# circuito_v4.net
KiCad netlist of a schematic drawn in EAGLE
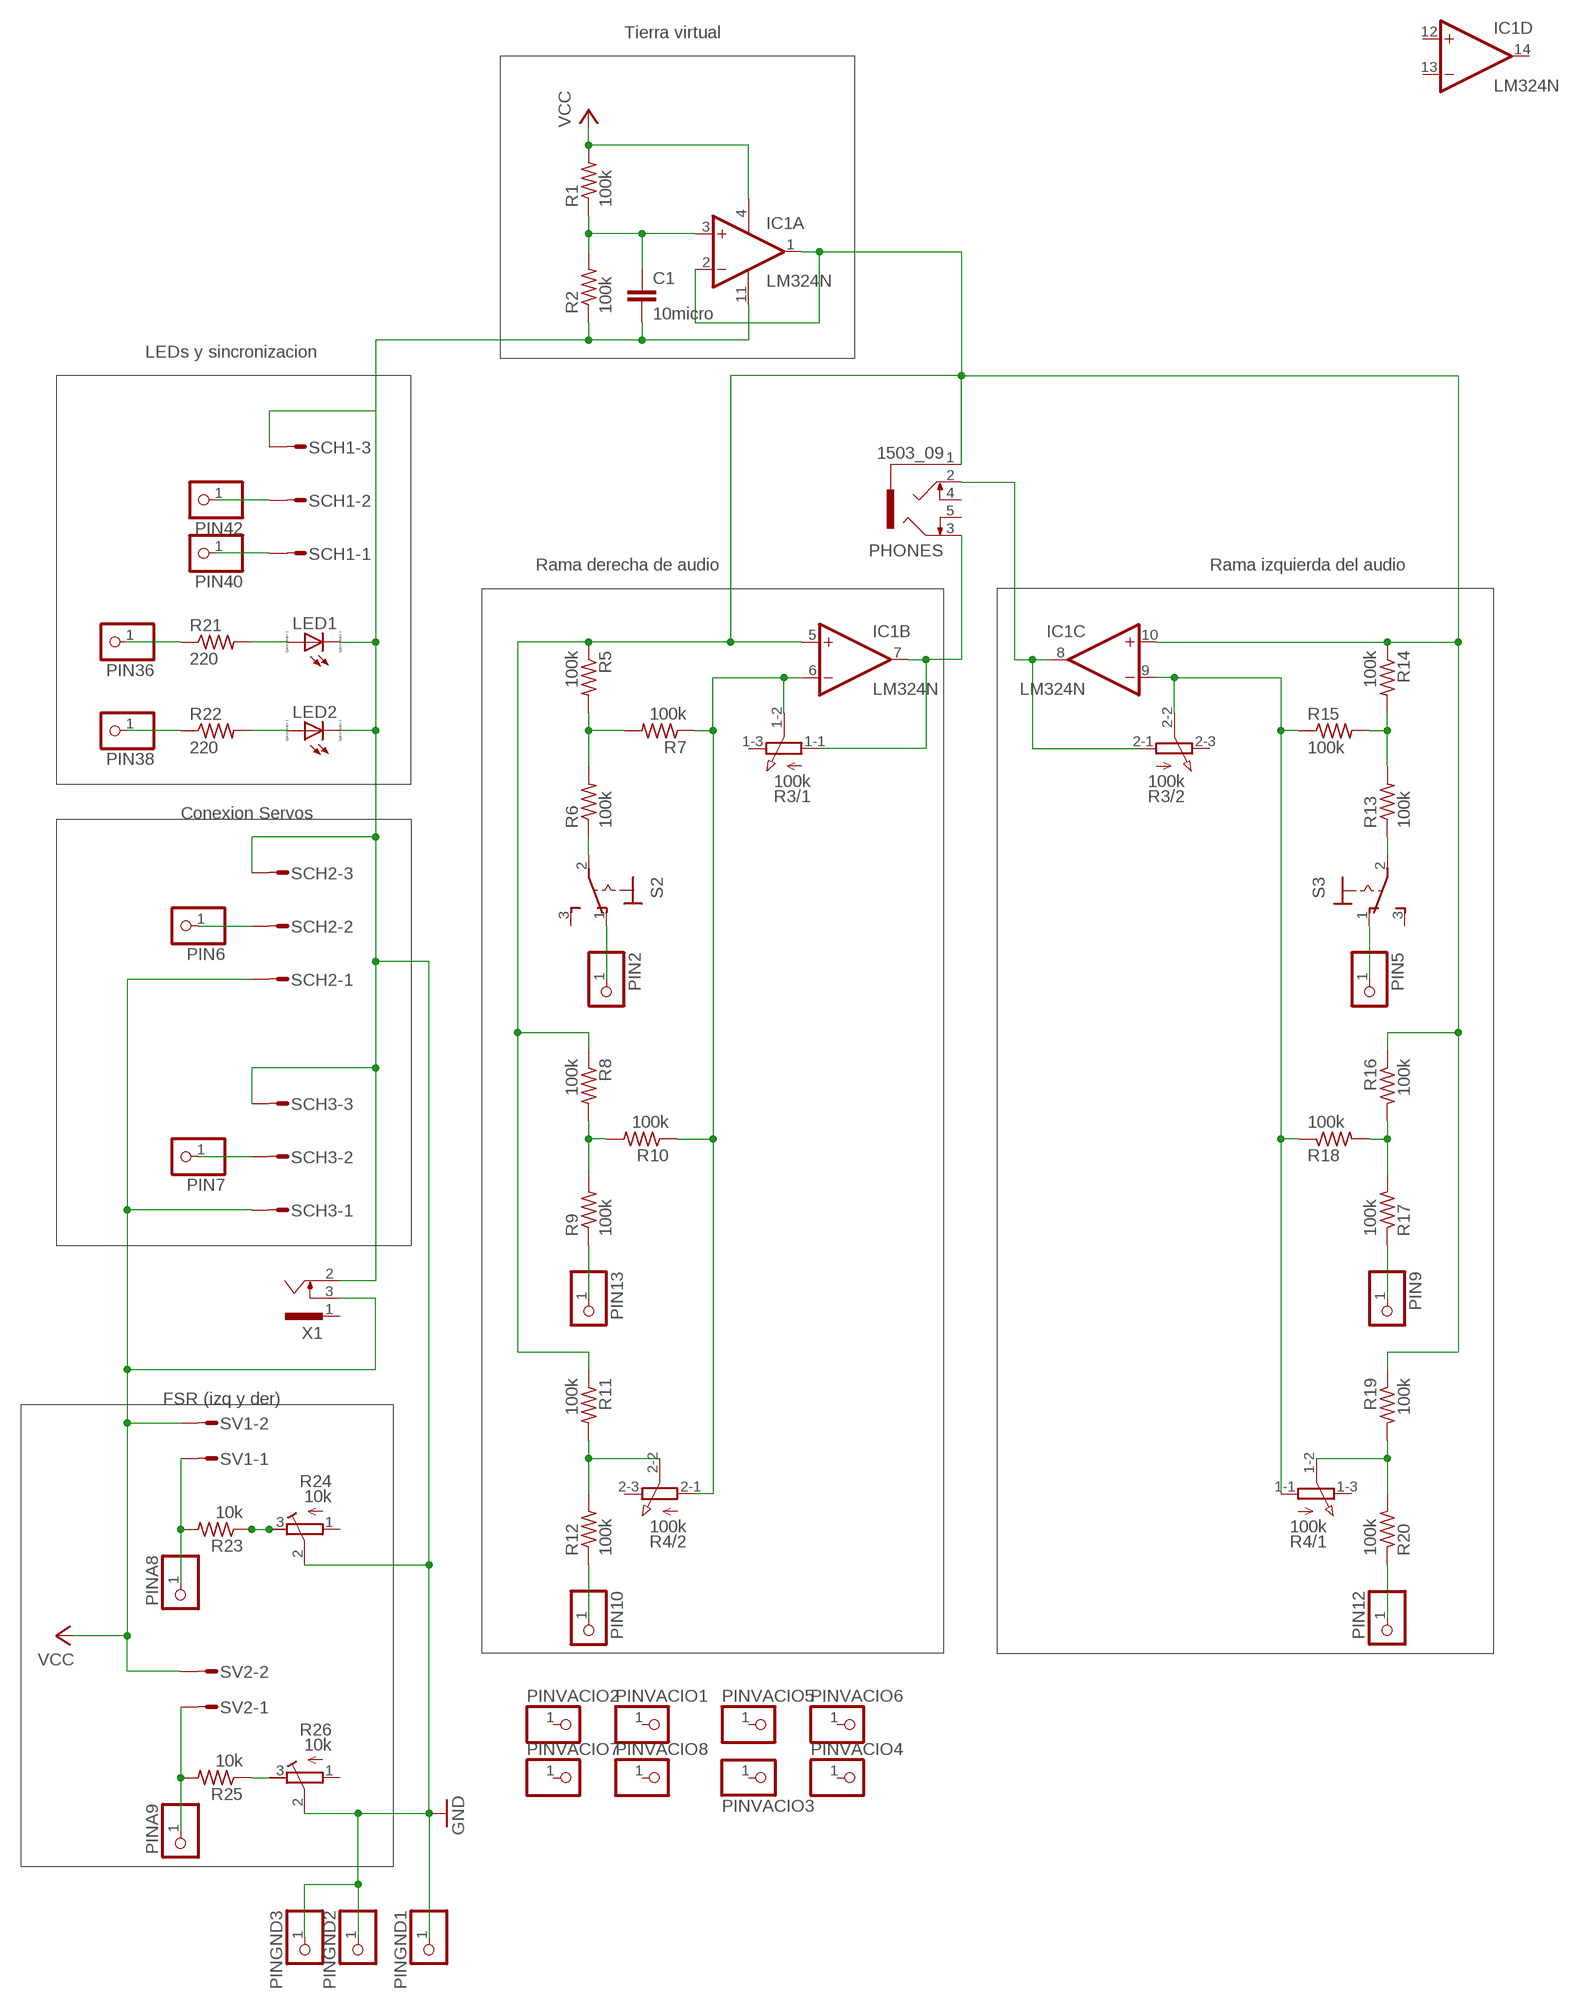
[diagram p0: schematic, sheet 1]
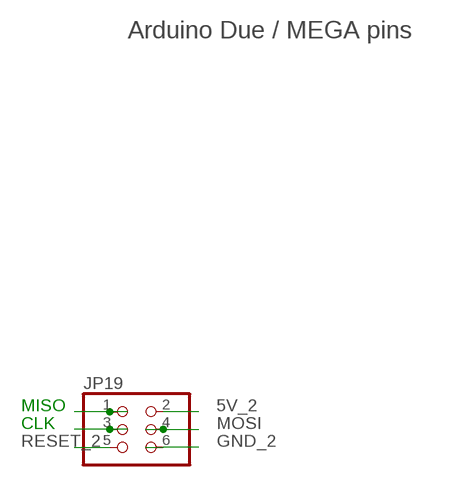
[diagram p1: schematic, sheet 2]

(export (version "E")
  (design (tool "Eeschema 10.0.6"))
  (components
    (comp (ref "JP19")
      (value "PINHD-2X3")
      (footprint "eagle-import:2X03")
      (libsource (lib "eagle-import") (part "PINHD-2X3"))
    )
    (comp (ref "C1")
      (value "10micro")
      (footprint "eagle-import:C025-030X050")
      (libsource (lib "eagle-import") (part "C-EU025-030X050"))
    )
    (comp (ref "IC1")
      (value "LM324N")
      (footprint "eagle-import:DIL14")
      (libsource (lib "eagle-import") (part "LM324N"))
    )
    (comp (ref "LED1")
      (value "LED_ELD260")
      (footprint "eagle-import:LED_LD260")
      (libsource (lib "eagle-import") (part "LED_ELD260"))
    )
    (comp (ref "LED2")
      (value "LED_ELD260")
      (footprint "eagle-import:LED_LD260")
      (libsource (lib "eagle-import") (part "LED_ELD260"))
    )
    (comp (ref "PHONES")
      (value "1503_09")
      (footprint "eagle-import:1503_09")
      (libsource (lib "eagle-import") (part "1503_09"))
    )
    (comp (ref "PIN2")
      (value "PINHD-1X1")
      (footprint "eagle-import:1X01")
      (libsource (lib "eagle-import") (part "PINHD-1X1"))
    )
    (comp (ref "PIN5")
      (value "PINHD-1X1")
      (footprint "eagle-import:1X01")
      (libsource (lib "eagle-import") (part "PINHD-1X1"))
    )
    (comp (ref "PIN6")
      (value "PINHD-1X1")
      (footprint "eagle-import:1X01")
      (libsource (lib "eagle-import") (part "PINHD-1X1"))
    )
    (comp (ref "PIN7")
      (value "PINHD-1X1")
      (footprint "eagle-import:1X01")
      (libsource (lib "eagle-import") (part "PINHD-1X1"))
    )
    (comp (ref "PIN9")
      (value "PINHD-1X1")
      (footprint "eagle-import:1X01")
      (libsource (lib "eagle-import") (part "PINHD-1X1"))
    )
    (comp (ref "PIN10")
      (value "PINHD-1X1")
      (footprint "eagle-import:1X01")
      (libsource (lib "eagle-import") (part "PINHD-1X1"))
    )
    (comp (ref "PIN12")
      (value "PINHD-1X1")
      (footprint "eagle-import:1X01")
      (libsource (lib "eagle-import") (part "PINHD-1X1"))
    )
    (comp (ref "PIN13")
      (value "PINHD-1X1")
      (footprint "eagle-import:1X01")
      (libsource (lib "eagle-import") (part "PINHD-1X1"))
    )
    (comp (ref "PIN36")
      (value "PINHD-1X1")
      (footprint "eagle-import:1X01")
      (libsource (lib "eagle-import") (part "PINHD-1X1"))
    )
    (comp (ref "PIN38")
      (value "PINHD-1X1")
      (footprint "eagle-import:1X01")
      (libsource (lib "eagle-import") (part "PINHD-1X1"))
    )
    (comp (ref "PIN40")
      (value "PINHD-1X1")
      (footprint "eagle-import:1X01")
      (libsource (lib "eagle-import") (part "PINHD-1X1"))
    )
    (comp (ref "PIN42")
      (value "PINHD-1X1")
      (footprint "eagle-import:1X01")
      (libsource (lib "eagle-import") (part "PINHD-1X1"))
    )
    (comp (ref "PINA8")
      (value "PINHD-1X1")
      (footprint "eagle-import:1X01")
      (libsource (lib "eagle-import") (part "PINHD-1X1"))
    )
    (comp (ref "PINA9")
      (value "PINHD-1X1")
      (footprint "eagle-import:1X01")
      (libsource (lib "eagle-import") (part "PINHD-1X1"))
    )
    (comp (ref "PINGND1")
      (value "PINHD-1X1")
      (footprint "eagle-import:1X01")
      (libsource (lib "eagle-import") (part "PINHD-1X1"))
    )
    (comp (ref "PINGND2")
      (value "PINHD-1X1")
      (footprint "eagle-import:1X01")
      (libsource (lib "eagle-import") (part "PINHD-1X1"))
    )
    (comp (ref "PINGND3")
      (value "PINHD-1X1")
      (footprint "eagle-import:1X01")
      (libsource (lib "eagle-import") (part "PINHD-1X1"))
    )
    (comp (ref "PINVACIO1")
      (value "PINHD-1X1")
      (footprint "eagle-import:1X01")
      (libsource (lib "eagle-import") (part "PINHD-1X1"))
    )
    (comp (ref "PINVACIO2")
      (value "PINHD-1X1")
      (footprint "eagle-import:1X01")
      (libsource (lib "eagle-import") (part "PINHD-1X1"))
    )
    (comp (ref "PINVACIO3")
      (value "PINHD-1X1")
      (footprint "eagle-import:1X01")
      (libsource (lib "eagle-import") (part "PINHD-1X1"))
    )
    (comp (ref "PINVACIO4")
      (value "PINHD-1X1")
      (footprint "eagle-import:1X01")
      (libsource (lib "eagle-import") (part "PINHD-1X1"))
    )
    (comp (ref "PINVACIO5")
      (value "PINHD-1X1")
      (footprint "eagle-import:1X01")
      (libsource (lib "eagle-import") (part "PINHD-1X1"))
    )
    (comp (ref "PINVACIO6")
      (value "PINHD-1X1")
      (footprint "eagle-import:1X01")
      (libsource (lib "eagle-import") (part "PINHD-1X1"))
    )
    (comp (ref "PINVACIO7")
      (value "PINHD-1X1")
      (footprint "eagle-import:1X01")
      (libsource (lib "eagle-import") (part "PINHD-1X1"))
    )
    (comp (ref "PINVACIO8")
      (value "PINHD-1X1")
      (footprint "eagle-import:1X01")
      (libsource (lib "eagle-import") (part "PINHD-1X1"))
    )
    (comp (ref "R1")
      (value "100k")
      (footprint "eagle-import:0207_7")
      (libsource (lib "eagle-import") (part "R-US_0207/7"))
    )
    (comp (ref "R2")
      (value "100k")
      (footprint "eagle-import:0207_7")
      (libsource (lib "eagle-import") (part "R-US_0207/7"))
    )
    (comp (ref "R3")
      (value "100k")
      (footprint "eagle-import:3RP_1610G")
      (libsource (lib "eagle-import") (part "3RP/1610G"))
    )
    (comp (ref "R4")
      (value "100k")
      (footprint "eagle-import:3RP_1610G")
      (libsource (lib "eagle-import") (part "3RP/1610G"))
    )
    (comp (ref "R5")
      (value "100k")
      (footprint "eagle-import:0207_7")
      (libsource (lib "eagle-import") (part "R-US_0207/7"))
    )
    (comp (ref "R6")
      (value "100k")
      (footprint "eagle-import:0207_7")
      (libsource (lib "eagle-import") (part "R-US_0207/7"))
    )
    (comp (ref "R7")
      (value "100k")
      (footprint "eagle-import:0207_7")
      (libsource (lib "eagle-import") (part "R-US_0207/7"))
    )
    (comp (ref "R8")
      (value "100k")
      (footprint "eagle-import:0207_7")
      (libsource (lib "eagle-import") (part "R-US_0207/7"))
    )
    (comp (ref "R9")
      (value "100k")
      (footprint "eagle-import:0207_7")
      (libsource (lib "eagle-import") (part "R-US_0207/7"))
    )
    (comp (ref "R10")
      (value "100k")
      (footprint "eagle-import:0207_7")
      (libsource (lib "eagle-import") (part "R-US_0207/7"))
    )
    (comp (ref "R11")
      (value "100k")
      (footprint "eagle-import:0207_7")
      (libsource (lib "eagle-import") (part "R-US_0207/7"))
    )
    (comp (ref "R12")
      (value "100k")
      (footprint "eagle-import:0207_7")
      (libsource (lib "eagle-import") (part "R-US_0207/7"))
    )
    (comp (ref "R13")
      (value "100k")
      (footprint "eagle-import:0207_7")
      (libsource (lib "eagle-import") (part "R-US_0207/7"))
    )
    (comp (ref "R14")
      (value "100k")
      (footprint "eagle-import:0207_7")
      (libsource (lib "eagle-import") (part "R-US_0207/7"))
    )
    (comp (ref "R15")
      (value "100k")
      (footprint "eagle-import:0207_7")
      (libsource (lib "eagle-import") (part "R-US_0207/7"))
    )
    (comp (ref "R16")
      (value "100k")
      (footprint "eagle-import:0207_7")
      (libsource (lib "eagle-import") (part "R-US_0207/7"))
    )
    (comp (ref "R17")
      (value "100k")
      (footprint "eagle-import:0207_7")
      (libsource (lib "eagle-import") (part "R-US_0207/7"))
    )
    (comp (ref "R18")
      (value "100k")
      (footprint "eagle-import:0207_7")
      (libsource (lib "eagle-import") (part "R-US_0207/7"))
    )
    (comp (ref "R19")
      (value "100k")
      (footprint "eagle-import:0207_7")
      (libsource (lib "eagle-import") (part "R-US_0207/7"))
    )
    (comp (ref "R20")
      (value "100k")
      (footprint "eagle-import:0207_7")
      (libsource (lib "eagle-import") (part "R-US_0207/7"))
    )
    (comp (ref "R21")
      (value "220")
      (footprint "eagle-import:0207_7")
      (libsource (lib "eagle-import") (part "R-US_0207/7"))
    )
    (comp (ref "R22")
      (value "220")
      (footprint "eagle-import:0207_7")
      (libsource (lib "eagle-import") (part "R-US_0207/7"))
    )
    (comp (ref "R23")
      (value "10k")
      (footprint "eagle-import:0207_7")
      (libsource (lib "eagle-import") (part "R-US_0207/7"))
    )
    (comp (ref "R24")
      (value "10k")
      (footprint "eagle-import:RTRIM64W")
      (libsource (lib "eagle-import") (part "R-TRIMM64W"))
    )
    (comp (ref "R25")
      (value "10k")
      (footprint "eagle-import:0207_7")
      (libsource (lib "eagle-import") (part "R-US_0207/7"))
    )
    (comp (ref "R26")
      (value "10k")
      (footprint "eagle-import:RTRIM64W")
      (libsource (lib "eagle-import") (part "R-TRIMM64W"))
    )
    (comp (ref "S2")
      (value "320-916")
      (footprint "eagle-import:320-916")
      (libsource (lib "eagle-import") (part "320-916"))
    )
    (comp (ref "S3")
      (value "320-916")
      (footprint "eagle-import:320-916")
      (libsource (lib "eagle-import") (part "320-916"))
    )
    (comp (ref "SCH1")
      (value "L03P")
      (footprint "eagle-import:L03P")
      (libsource (lib "eagle-import") (part "L03P"))
    )
    (comp (ref "SCH2")
      (value "L03P")
      (footprint "eagle-import:L03P")
      (libsource (lib "eagle-import") (part "L03P"))
    )
    (comp (ref "SCH3")
      (value "L03P")
      (footprint "eagle-import:L03P")
      (libsource (lib "eagle-import") (part "L03P"))
    )
    (comp (ref "SV1")
      (value "L02P")
      (footprint "eagle-import:L02P")
      (libsource (lib "eagle-import") (part "L02P"))
    )
    (comp (ref "SV2")
      (value "L02P")
      (footprint "eagle-import:L02P")
      (libsource (lib "eagle-import") (part "L02P"))
    )
    (comp (ref "X1")
      (value "SCD-014A")
      (footprint "eagle-import:SCD-014-A")
      (libsource (lib "eagle-import") (part "SCD-014A"))
    )
  )
  (nets
    (net (code "1") (name "5V_2") (class "Default")
      (node (ref "JP19") (pin "2") (pinfunction "2_2") (pintype "passive"))
    )
    (net (code "2") (name "CLK") (class "Default")
      (node (ref "JP19") (pin "3") (pinfunction "3_3") (pintype "passive"))
    )
    (net (code "3") (name "GND") (class "Default")
      (node (ref "C1") (pin "2") (pinfunction "2_2") (pintype "passive"))
      (node (ref "IC1") (pin "11") (pinfunction "V-_11") (pintype "power_in"))
      (node (ref "LED1") (pin "K") (pinfunction "C_K") (pintype "passive"))
      (node (ref "LED2") (pin "K") (pinfunction "C_K") (pintype "passive"))
      (node (ref "PINGND1") (pin "1") (pinfunction "1_1") (pintype "passive"))
      (node (ref "PINGND2") (pin "1") (pinfunction "1_1") (pintype "passive"))
      (node (ref "PINGND3") (pin "1") (pinfunction "1_1") (pintype "passive"))
      (node (ref "R2") (pin "1") (pinfunction "1_1") (pintype "passive"))
      (node (ref "R24") (pin "2") (pinfunction "S_2") (pintype "passive"))
      (node (ref "R26") (pin "2") (pinfunction "S_2") (pintype "passive"))
      (node (ref "SCH1") (pin "3") (pinfunction "S_3") (pintype "passive"))
      (node (ref "SCH2") (pin "3") (pinfunction "S_3") (pintype "passive"))
      (node (ref "SCH3") (pin "3") (pinfunction "S_3") (pintype "passive"))
      (node (ref "X1") (pin "2") (pinfunction "2_2") (pintype "passive"))
    )
    (net (code "4") (name "GND_2") (class "Default")
      (node (ref "JP19") (pin "6") (pinfunction "6_6") (pintype "passive"))
    )
    (net (code "5") (name "MISO") (class "Default")
      (node (ref "JP19") (pin "1") (pinfunction "1_1") (pintype "passive"))
    )
    (net (code "6") (name "MOSI") (class "Default")
      (node (ref "JP19") (pin "4") (pinfunction "4_4") (pintype "passive"))
    )
    (net (code "7") (name "Net-(IC1A-+IN)") (class "Default")
      (node (ref "C1") (pin "1") (pinfunction "1_1") (pintype "passive"))
      (node (ref "IC1") (pin "3") (pinfunction "+IN_3") (pintype "input"))
      (node (ref "R1") (pin "1") (pinfunction "1_1") (pintype "passive"))
      (node (ref "R2") (pin "2") (pinfunction "2_2") (pintype "passive"))
    )
    (net (code "8") (name "Net-(IC1A--IN)") (class "Default")
      (node (ref "IC1") (pin "1") (pinfunction "OUT_1") (pintype "output"))
      (node (ref "IC1") (pin "10") (pinfunction "+IN_10") (pintype "input"))
      (node (ref "IC1") (pin "2") (pinfunction "-IN_2") (pintype "input"))
      (node (ref "IC1") (pin "5") (pinfunction "+IN_5") (pintype "input"))
      (node (ref "PHONES") (pin "1") (pinfunction "1_1") (pintype "passive"))
      (node (ref "R11") (pin "1") (pinfunction "1_1") (pintype "passive"))
      (node (ref "R14") (pin "1") (pinfunction "1_1") (pintype "passive"))
      (node (ref "R16") (pin "1") (pinfunction "1_1") (pintype "passive"))
      (node (ref "R19") (pin "1") (pinfunction "1_1") (pintype "passive"))
      (node (ref "R5") (pin "1") (pinfunction "1_1") (pintype "passive"))
      (node (ref "R8") (pin "1") (pinfunction "1_1") (pintype "passive"))
    )
    (net (code "9") (name "Net-(IC1B--IN)") (class "Default")
      (node (ref "IC1") (pin "6") (pinfunction "-IN_6") (pintype "input"))
      (node (ref "R10") (pin "1") (pinfunction "1_1") (pintype "passive"))
      (node (ref "R3") (pin "1-2") (pinfunction "S_1-2") (pintype "passive"))
      (node (ref "R4") (pin "2-1") (pinfunction "A_2-1") (pintype "passive"))
      (node (ref "R7") (pin "1") (pinfunction "1_1") (pintype "passive"))
    )
    (net (code "10") (name "Net-(IC1B-OUT)") (class "Default")
      (node (ref "IC1") (pin "7") (pinfunction "OUT_7") (pintype "output"))
      (node (ref "PHONES") (pin "3") (pinfunction "3_3") (pintype "passive"))
      (node (ref "R3") (pin "1-1") (pinfunction "A_1-1") (pintype "passive"))
    )
    (net (code "11") (name "Net-(IC1C--IN)") (class "Default")
      (node (ref "IC1") (pin "9") (pinfunction "-IN_9") (pintype "input"))
      (node (ref "R15") (pin "1") (pinfunction "1_1") (pintype "passive"))
      (node (ref "R18") (pin "1") (pinfunction "1_1") (pintype "passive"))
      (node (ref "R3") (pin "2-2") (pinfunction "S_2-2") (pintype "passive"))
      (node (ref "R4") (pin "1-1") (pinfunction "A_1-1") (pintype "passive"))
    )
    (net (code "12") (name "Net-(IC1C-OUT)") (class "Default")
      (node (ref "IC1") (pin "8") (pinfunction "OUT_8") (pintype "output"))
      (node (ref "PHONES") (pin "2") (pinfunction "2_2") (pintype "passive"))
      (node (ref "R3") (pin "2-1") (pinfunction "A_2-1") (pintype "passive"))
    )
    (net (code "13") (name "Net-(LED1-PadA)") (class "Default")
      (node (ref "LED1") (pin "A") (pinfunction "A_A") (pintype "passive"))
      (node (ref "R21") (pin "2") (pinfunction "2_2") (pintype "passive"))
    )
    (net (code "14") (name "Net-(LED2-PadA)") (class "Default")
      (node (ref "LED2") (pin "A") (pinfunction "A_A") (pintype "passive"))
      (node (ref "R22") (pin "2") (pinfunction "2_2") (pintype "passive"))
    )
    (net (code "15") (name "Net-(PIN9-Pad1)") (class "Default")
      (node (ref "PIN9") (pin "1") (pinfunction "1_1") (pintype "passive"))
      (node (ref "R17") (pin "1") (pinfunction "1_1") (pintype "passive"))
    )
    (net (code "16") (name "Net-(PIN10-Pad1)") (class "Default")
      (node (ref "PIN10") (pin "1") (pinfunction "1_1") (pintype "passive"))
      (node (ref "R12") (pin "1") (pinfunction "1_1") (pintype "passive"))
    )
    (net (code "17") (name "Net-(PIN12-Pad1)") (class "Default")
      (node (ref "PIN12") (pin "1") (pinfunction "1_1") (pintype "passive"))
      (node (ref "R20") (pin "1") (pinfunction "1_1") (pintype "passive"))
    )
    (net (code "18") (name "Net-(PIN13-Pad1)") (class "Default")
      (node (ref "PIN13") (pin "1") (pinfunction "1_1") (pintype "passive"))
      (node (ref "R9") (pin "1") (pinfunction "1_1") (pintype "passive"))
    )
    (net (code "19") (name "Net-(PIN36-Pad1)") (class "Default")
      (node (ref "PIN36") (pin "1") (pinfunction "1_1") (pintype "passive"))
      (node (ref "R21") (pin "1") (pinfunction "1_1") (pintype "passive"))
    )
    (net (code "20") (name "Net-(PIN38-Pad1)") (class "Default")
      (node (ref "PIN38") (pin "1") (pinfunction "1_1") (pintype "passive"))
      (node (ref "R22") (pin "1") (pinfunction "1_1") (pintype "passive"))
    )
    (net (code "21") (name "Net-(R4A-S)") (class "Default")
      (node (ref "R19") (pin "2") (pinfunction "2_2") (pintype "passive"))
      (node (ref "R20") (pin "2") (pinfunction "2_2") (pintype "passive"))
      (node (ref "R4") (pin "1-2") (pinfunction "S_1-2") (pintype "passive"))
    )
    (net (code "22") (name "Net-(R4B-S)") (class "Default")
      (node (ref "R11") (pin "2") (pinfunction "2_2") (pintype "passive"))
      (node (ref "R12") (pin "2") (pinfunction "2_2") (pintype "passive"))
      (node (ref "R4") (pin "2-2") (pinfunction "S_2-2") (pintype "passive"))
    )
    (net (code "23") (name "Net-(R5-Pad2)") (class "Default")
      (node (ref "R5") (pin "2") (pinfunction "2_2") (pintype "passive"))
      (node (ref "R6") (pin "2") (pinfunction "2_2") (pintype "passive"))
      (node (ref "R7") (pin "2") (pinfunction "2_2") (pintype "passive"))
    )
    (net (code "24") (name "Net-(R10-Pad2)") (class "Default")
      (node (ref "R10") (pin "2") (pinfunction "2_2") (pintype "passive"))
      (node (ref "R8") (pin "2") (pinfunction "2_2") (pintype "passive"))
      (node (ref "R9") (pin "2") (pinfunction "2_2") (pintype "passive"))
    )
    (net (code "25") (name "Net-(R13-Pad2)") (class "Default")
      (node (ref "R13") (pin "2") (pinfunction "2_2") (pintype "passive"))
      (node (ref "R14") (pin "2") (pinfunction "2_2") (pintype "passive"))
      (node (ref "R15") (pin "2") (pinfunction "2_2") (pintype "passive"))
    )
    (net (code "26") (name "Net-(R16-Pad2)") (class "Default")
      (node (ref "R16") (pin "2") (pinfunction "2_2") (pintype "passive"))
      (node (ref "R17") (pin "2") (pinfunction "2_2") (pintype "passive"))
      (node (ref "R18") (pin "2") (pinfunction "2_2") (pintype "passive"))
    )
    (net (code "27") (name "Net-(R24-E)") (class "Default")
      (node (ref "R23") (pin "1") (pinfunction "1_1") (pintype "passive"))
      (node (ref "R24") (pin "3") (pinfunction "E_3") (pintype "passive"))
    )
    (net (code "28") (name "Net-(R26-E)") (class "Default")
      (node (ref "R25") (pin "1") (pinfunction "1_1") (pintype "passive"))
      (node (ref "R26") (pin "3") (pinfunction "E_3") (pintype "passive"))
    )
    (net (code "29") (name "Net-(S2-O)") (class "Default")
      (node (ref "PIN2") (pin "1") (pinfunction "1_1") (pintype "passive"))
      (node (ref "S2") (pin "1") (pinfunction "O_1") (pintype "passive"))
    )
    (net (code "30") (name "Net-(S2-P)") (class "Default")
      (node (ref "R6") (pin "1") (pinfunction "1_1") (pintype "passive"))
      (node (ref "S2") (pin "2") (pinfunction "P_2") (pintype "passive"))
    )
    (net (code "31") (name "Net-(S3-O)") (class "Default")
      (node (ref "PIN5") (pin "1") (pinfunction "1_1") (pintype "passive"))
      (node (ref "S3") (pin "1") (pinfunction "O_1") (pintype "passive"))
    )
    (net (code "32") (name "Net-(S3-P)") (class "Default")
      (node (ref "R13") (pin "1") (pinfunction "1_1") (pintype "passive"))
      (node (ref "S3") (pin "2") (pinfunction "P_2") (pintype "passive"))
    )
    (net (code "33") (name "Net-(SCH1A-S)") (class "Default")
      (node (ref "PIN40") (pin "1") (pinfunction "1_1") (pintype "passive"))
      (node (ref "SCH1") (pin "1") (pinfunction "S_1") (pintype "passive"))
    )
    (net (code "34") (name "Net-(SCH1B-S)") (class "Default")
      (node (ref "PIN42") (pin "1") (pinfunction "1_1") (pintype "passive"))
      (node (ref "SCH1") (pin "2") (pinfunction "S_2") (pintype "passive"))
    )
    (net (code "35") (name "Net-(SCH2B-S)") (class "Default")
      (node (ref "PIN6") (pin "1") (pinfunction "1_1") (pintype "passive"))
      (node (ref "SCH2") (pin "2") (pinfunction "S_2") (pintype "passive"))
    )
    (net (code "36") (name "Net-(SCH3B-S)") (class "Default")
      (node (ref "PIN7") (pin "1") (pinfunction "1_1") (pintype "passive"))
      (node (ref "SCH3") (pin "2") (pinfunction "S_2") (pintype "passive"))
    )
    (net (code "37") (name "Net-(SV1A-S)") (class "Default")
      (node (ref "PINA8") (pin "1") (pinfunction "1_1") (pintype "passive"))
      (node (ref "R23") (pin "2") (pinfunction "2_2") (pintype "passive"))
      (node (ref "SV1") (pin "1") (pinfunction "S_1") (pintype "passive"))
    )
    (net (code "38") (name "Net-(SV2A-S)") (class "Default")
      (node (ref "PINA9") (pin "1") (pinfunction "1_1") (pintype "passive"))
      (node (ref "R25") (pin "2") (pinfunction "2_2") (pintype "passive"))
      (node (ref "SV2") (pin "1") (pinfunction "S_1") (pintype "passive"))
    )
    (net (code "39") (name "RESET_2") (class "Default")
      (node (ref "JP19") (pin "5") (pinfunction "5_5") (pintype "passive"))
    )
    (net (code "40") (name "VCC") (class "Default")
      (node (ref "IC1") (pin "4") (pinfunction "V+_4") (pintype "power_in"))
      (node (ref "R1") (pin "2") (pinfunction "2_2") (pintype "passive"))
      (node (ref "SCH2") (pin "1") (pinfunction "S_1") (pintype "passive"))
      (node (ref "SCH3") (pin "1") (pinfunction "S_1") (pintype "passive"))
      (node (ref "SV1") (pin "2") (pinfunction "S_2") (pintype "passive"))
      (node (ref "SV2") (pin "2") (pinfunction "S_2") (pintype "passive"))
      (node (ref "X1") (pin "3") (pinfunction "3_3") (pintype "passive"))
    )
    (net (code "41") (name "unconnected-(IC1D-+IN-Pad12)") (class "Default")
      (node (ref "IC1") (pin "12") (pinfunction "+IN_12") (pintype "input"))
    )
    (net (code "42") (name "unconnected-(IC1D--IN-Pad13)") (class "Default")
      (node (ref "IC1") (pin "13") (pinfunction "-IN_13") (pintype "input"))
    )
    (net (code "43") (name "unconnected-(IC1D-OUT-Pad14)") (class "Default")
      (node (ref "IC1") (pin "14") (pinfunction "OUT_14") (pintype "output"))
    )
    (net (code "44") (name "unconnected-(PHONES-Pad4)") (class "Default")
      (node (ref "PHONES") (pin "4") (pinfunction "4_4") (pintype "passive"))
    )
    (net (code "45") (name "unconnected-(PHONES-Pad5)") (class "Default")
      (node (ref "PHONES") (pin "5") (pinfunction "5_5") (pintype "passive"))
    )
    (net (code "46") (name "unconnected-(PINVACIO1-Pad1)") (class "Default")
      (node (ref "PINVACIO1") (pin "1") (pinfunction "1_1") (pintype "passive"))
    )
    (net (code "47") (name "unconnected-(PINVACIO2-Pad1)") (class "Default")
      (node (ref "PINVACIO2") (pin "1") (pinfunction "1_1") (pintype "passive"))
    )
    (net (code "48") (name "unconnected-(PINVACIO3-Pad1)") (class "Default")
      (node (ref "PINVACIO3") (pin "1") (pinfunction "1_1") (pintype "passive"))
    )
    (net (code "49") (name "unconnected-(PINVACIO4-Pad1)") (class "Default")
      (node (ref "PINVACIO4") (pin "1") (pinfunction "1_1") (pintype "passive"))
    )
    (net (code "50") (name "unconnected-(PINVACIO5-Pad1)") (class "Default")
      (node (ref "PINVACIO5") (pin "1") (pinfunction "1_1") (pintype "passive"))
    )
    (net (code "51") (name "unconnected-(PINVACIO6-Pad1)") (class "Default")
      (node (ref "PINVACIO6") (pin "1") (pinfunction "1_1") (pintype "passive"))
    )
    (net (code "52") (name "unconnected-(PINVACIO7-Pad1)") (class "Default")
      (node (ref "PINVACIO7") (pin "1") (pinfunction "1_1") (pintype "passive"))
    )
    (net (code "53") (name "unconnected-(PINVACIO8-Pad1)") (class "Default")
      (node (ref "PINVACIO8") (pin "1") (pinfunction "1_1") (pintype "passive"))
    )
    (net (code "54") (name "unconnected-(R3A-E-Pad1-3)") (class "Default")
      (node (ref "R3") (pin "1-3") (pinfunction "E_1-3") (pintype "passive"))
    )
    (net (code "55") (name "unconnected-(R3B-E-Pad2-3)") (class "Default")
      (node (ref "R3") (pin "2-3") (pinfunction "E_2-3") (pintype "passive"))
    )
    (net (code "56") (name "unconnected-(R4A-E-Pad1-3)") (class "Default")
      (node (ref "R4") (pin "1-3") (pinfunction "E_1-3") (pintype "passive"))
    )
    (net (code "57") (name "unconnected-(R4B-E-Pad2-3)") (class "Default")
      (node (ref "R4") (pin "2-3") (pinfunction "E_2-3") (pintype "passive"))
    )
    (net (code "58") (name "unconnected-(R24-A-Pad1)") (class "Default")
      (node (ref "R24") (pin "1") (pinfunction "A_1") (pintype "passive"))
    )
    (net (code "59") (name "unconnected-(R26-A-Pad1)") (class "Default")
      (node (ref "R26") (pin "1") (pinfunction "A_1") (pintype "passive"))
    )
    (net (code "60") (name "unconnected-(S2-S-Pad3)") (class "Default")
      (node (ref "S2") (pin "3") (pinfunction "S_3") (pintype "passive"))
    )
    (net (code "61") (name "unconnected-(S3-S-Pad3)") (class "Default")
      (node (ref "S3") (pin "3") (pinfunction "S_3") (pintype "passive"))
    )
    (net (code "62") (name "unconnected-(X1-Pad1)") (class "Default")
      (node (ref "X1") (pin "1") (pinfunction "1_1") (pintype "passive"))
    )
  )
)
